# untitled2.net
KiCad netlist of a schematic drawn in EAGLE
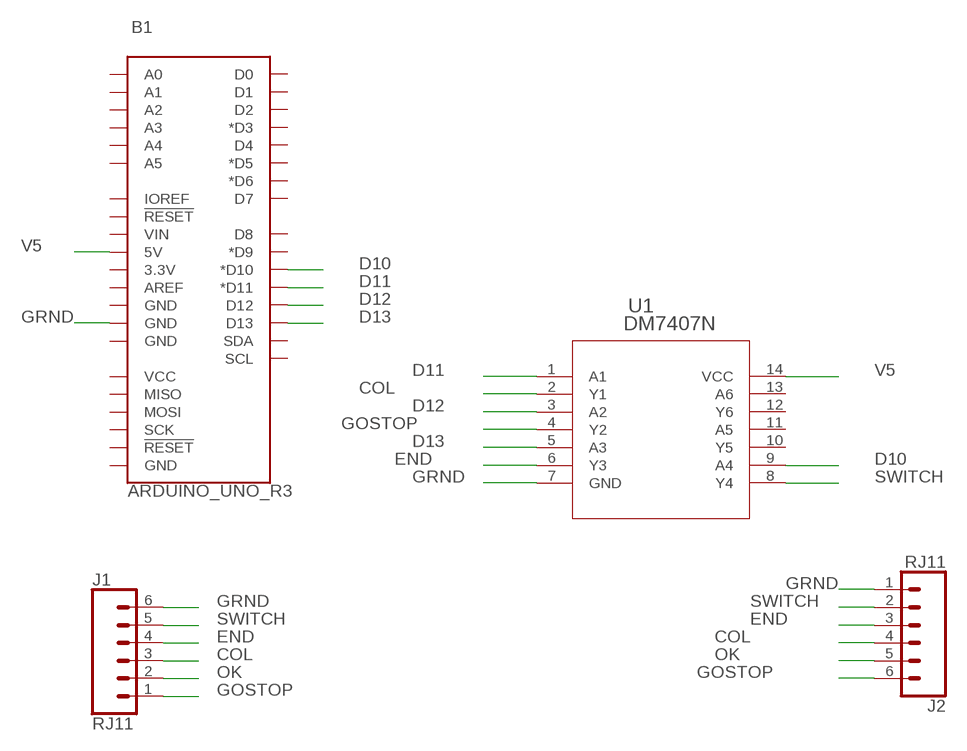
[diagram p0: schematic, sheet 1]

(export (version "E")
  (design (tool "Eeschema 10.0.6"))
  (components
    (comp (ref "B1")
      (value "ARDUINO_UNO_R3")
      (footprint "eagle-import:ARDUINO_R3")
      (libsource (lib "eagle-import") (part "ARDUINO_UNO_R3"))
    )
    (comp (ref "J1")
      (value "RJ11")
      (footprint "eagle-import:RJ11-6")
      (libsource (lib "eagle-import") (part "RJ11-6"))
    )
    (comp (ref "J2")
      (value "RJ11")
      (footprint "eagle-import:RJ11-6")
      (libsource (lib "eagle-import") (part "RJ11-6"))
    )
    (comp (ref "U1")
      (value "DM7407N")
      (footprint "eagle-import:PDIP14_6P35X19P56_ONS")
      (fields (field (name "COPYRIGHT") "Copyright (C) 2024 Ultra Librarian. All rights reserved."))
      (libsource (lib "eagle-import") (part "DM7407N"))
    )
  )
  (nets
    (net (code "1") (name "/COL") (class "Default")
      (node (ref "J1") (pin "3") (pinfunction "3_3") (pintype "passive"))
      (node (ref "J2") (pin "4") (pinfunction "4_4") (pintype "passive"))
      (node (ref "U1") (pin "2") (pinfunction "Y1_2") (pintype "output"))
    )
    (net (code "2") (name "/D10") (class "Default")
      (node (ref "B1") (pin "D10") (pinfunction "*D10_D10") (pintype "bidirectional"))
      (node (ref "U1") (pin "9") (pinfunction "A4_9") (pintype "input"))
    )
    (net (code "3") (name "/D11") (class "Default")
      (node (ref "B1") (pin "D11") (pinfunction "*D11_D11") (pintype "bidirectional"))
      (node (ref "U1") (pin "1") (pinfunction "A1_1") (pintype "input"))
    )
    (net (code "4") (name "/D12") (class "Default")
      (node (ref "B1") (pin "D12") (pinfunction "D12_D12") (pintype "bidirectional"))
      (node (ref "U1") (pin "3") (pinfunction "A2_3") (pintype "input"))
    )
    (net (code "5") (name "/D13") (class "Default")
      (node (ref "B1") (pin "D13") (pinfunction "D13_D13") (pintype "bidirectional"))
      (node (ref "U1") (pin "5") (pinfunction "A3_5") (pintype "input"))
    )
    (net (code "6") (name "/END") (class "Default")
      (node (ref "J1") (pin "4") (pinfunction "4_4") (pintype "passive"))
      (node (ref "J2") (pin "3") (pinfunction "3_3") (pintype "passive"))
      (node (ref "U1") (pin "6") (pinfunction "Y3_6") (pintype "output"))
    )
    (net (code "7") (name "/GOSTOP") (class "Default")
      (node (ref "J1") (pin "1") (pinfunction "1_1") (pintype "passive"))
      (node (ref "J2") (pin "6") (pinfunction "6_6") (pintype "passive"))
      (node (ref "U1") (pin "4") (pinfunction "Y2_4") (pintype "output"))
    )
    (net (code "8") (name "/GRND") (class "Default")
      (node (ref "B1") (pin "GND@3") (pinfunction "GND_GND@3") (pintype "bidirectional"))
      (node (ref "J1") (pin "6") (pinfunction "6_6") (pintype "passive"))
      (node (ref "J2") (pin "1") (pinfunction "1_1") (pintype "passive"))
      (node (ref "U1") (pin "7") (pinfunction "GND_7") (pintype "power_in"))
    )
    (net (code "9") (name "/OK") (class "Default")
      (node (ref "J1") (pin "2") (pinfunction "2_2") (pintype "passive"))
      (node (ref "J2") (pin "5") (pinfunction "5_5") (pintype "passive"))
    )
    (net (code "10") (name "/SWITCH") (class "Default")
      (node (ref "J1") (pin "5") (pinfunction "5_5") (pintype "passive"))
      (node (ref "J2") (pin "2") (pinfunction "2_2") (pintype "passive"))
      (node (ref "U1") (pin "8") (pinfunction "Y4_8") (pintype "output"))
    )
    (net (code "11") (name "/V5") (class "Default")
      (node (ref "B1") (pin "5V") (pinfunction "5V_5V") (pintype "bidirectional"))
      (node (ref "U1") (pin "14") (pinfunction "VCC_14") (pintype "power_in"))
    )
    (net (code "12") (name "unconnected-(B1-*D3-PadD3)") (class "Default")
      (node (ref "B1") (pin "D3") (pinfunction "*D3_D3") (pintype "bidirectional"))
    )
    (net (code "13") (name "unconnected-(B1-*D5-PadD5)") (class "Default")
      (node (ref "B1") (pin "D5") (pinfunction "*D5_D5") (pintype "bidirectional"))
    )
    (net (code "14") (name "unconnected-(B1-*D6-PadD6)") (class "Default")
      (node (ref "B1") (pin "D6") (pinfunction "*D6_D6") (pintype "bidirectional"))
    )
    (net (code "15") (name "unconnected-(B1-*D9-PadD9)") (class "Default")
      (node (ref "B1") (pin "D9") (pinfunction "*D9_D9") (pintype "bidirectional"))
    )
    (net (code "16") (name "unconnected-(B1-GND-PadGND@1)") (class "Default")
      (node (ref "B1") (pin "GND@1") (pinfunction "GND_GND@1") (pintype "bidirectional"))
    )
    (net (code "17") (name "unconnected-(B1-GND-PadGND@2)") (class "Default")
      (node (ref "B1") (pin "GND@2") (pinfunction "GND_GND@2") (pintype "bidirectional"))
    )
    (net (code "18") (name "unconnected-(B1-GND-PadGND@4)") (class "Default")
      (node (ref "B1") (pin "GND@4") (pinfunction "GND_GND@4") (pintype "bidirectional"))
    )
    (net (code "19") (name "unconnected-(B1-Pad3.3V)") (class "Default")
      (node (ref "B1") (pin "3.3V") (pinfunction "3.3V_3.3V") (pintype "bidirectional"))
    )
    (net (code "20") (name "unconnected-(B1-PadA0)") (class "Default")
      (node (ref "B1") (pin "A0") (pinfunction "A0_A0") (pintype "bidirectional"))
    )
    (net (code "21") (name "unconnected-(B1-PadA1)") (class "Default")
      (node (ref "B1") (pin "A1") (pinfunction "A1_A1") (pintype "bidirectional"))
    )
    (net (code "22") (name "unconnected-(B1-PadA2)") (class "Default")
      (node (ref "B1") (pin "A2") (pinfunction "A2_A2") (pintype "bidirectional"))
    )
    (net (code "23") (name "unconnected-(B1-PadA3)") (class "Default")
      (node (ref "B1") (pin "A3") (pinfunction "A3_A3") (pintype "bidirectional"))
    )
    (net (code "24") (name "unconnected-(B1-PadA4)") (class "Default")
      (node (ref "B1") (pin "A4") (pinfunction "A4_A4") (pintype "bidirectional"))
    )
    (net (code "25") (name "unconnected-(B1-PadA5)") (class "Default")
      (node (ref "B1") (pin "A5") (pinfunction "A5_A5") (pintype "bidirectional"))
    )
    (net (code "26") (name "unconnected-(B1-PadAREF)") (class "Default")
      (node (ref "B1") (pin "AREF") (pinfunction "AREF_AREF") (pintype "bidirectional"))
    )
    (net (code "27") (name "unconnected-(B1-PadD0)") (class "Default")
      (node (ref "B1") (pin "D0") (pinfunction "D0_D0") (pintype "bidirectional"))
    )
    (net (code "28") (name "unconnected-(B1-PadD1)") (class "Default")
      (node (ref "B1") (pin "D1") (pinfunction "D1_D1") (pintype "bidirectional"))
    )
    (net (code "29") (name "unconnected-(B1-PadD2)") (class "Default")
      (node (ref "B1") (pin "D2") (pinfunction "D2_D2") (pintype "bidirectional"))
    )
    (net (code "30") (name "unconnected-(B1-PadD4)") (class "Default")
      (node (ref "B1") (pin "D4") (pinfunction "D4_D4") (pintype "bidirectional"))
    )
    (net (code "31") (name "unconnected-(B1-PadD7)") (class "Default")
      (node (ref "B1") (pin "D7") (pinfunction "D7_D7") (pintype "bidirectional"))
    )
    (net (code "32") (name "unconnected-(B1-PadD8)") (class "Default")
      (node (ref "B1") (pin "D8") (pinfunction "D8_D8") (pintype "bidirectional"))
    )
    (net (code "33") (name "unconnected-(B1-PadIOREF)") (class "Default")
      (node (ref "B1") (pin "IOREF") (pinfunction "IOREF_IOREF") (pintype "bidirectional"))
    )
    (net (code "34") (name "unconnected-(B1-PadMISO)") (class "Default")
      (node (ref "B1") (pin "MISO") (pinfunction "MISO_MISO") (pintype "bidirectional"))
    )
    (net (code "35") (name "unconnected-(B1-PadMOSI)") (class "Default")
      (node (ref "B1") (pin "MOSI") (pinfunction "MOSI_MOSI") (pintype "bidirectional"))
    )
    (net (code "36") (name "unconnected-(B1-PadSCK)") (class "Default")
      (node (ref "B1") (pin "SCK") (pinfunction "SCK_SCK") (pintype "bidirectional"))
    )
    (net (code "37") (name "unconnected-(B1-PadSCL)") (class "Default")
      (node (ref "B1") (pin "SCL") (pinfunction "SCL_SCL") (pintype "bidirectional"))
    )
    (net (code "38") (name "unconnected-(B1-PadSDA)") (class "Default")
      (node (ref "B1") (pin "SDA") (pinfunction "SDA_SDA") (pintype "bidirectional"))
    )
    (net (code "39") (name "unconnected-(B1-PadVCC)") (class "Default")
      (node (ref "B1") (pin "VCC") (pinfunction "VCC_VCC") (pintype "bidirectional"))
    )
    (net (code "40") (name "unconnected-(B1-PadVIN)") (class "Default")
      (node (ref "B1") (pin "VIN") (pinfunction "VIN_VIN") (pintype "bidirectional"))
    )
    (net (code "41") (name "unconnected-(B1-~{RESET}-PadRESET@1)") (class "Default")
      (node (ref "B1") (pin "RESET@1") (pinfunction "~{RESET}_RESET@1") (pintype "bidirectional"))
    )
    (net (code "42") (name "unconnected-(B1-~{RESET}-PadRESET@2)") (class "Default")
      (node (ref "B1") (pin "RESET@2") (pinfunction "~{RESET}_RESET@2") (pintype "bidirectional"))
    )
    (net (code "43") (name "unconnected-(U1-A5-Pad11)") (class "Default")
      (node (ref "U1") (pin "11") (pinfunction "A5_11") (pintype "input"))
    )
    (net (code "44") (name "unconnected-(U1-A6-Pad13)") (class "Default")
      (node (ref "U1") (pin "13") (pinfunction "A6_13") (pintype "input"))
    )
    (net (code "45") (name "unconnected-(U1-Y5-Pad10)") (class "Default")
      (node (ref "U1") (pin "10") (pinfunction "Y5_10") (pintype "output"))
    )
    (net (code "46") (name "unconnected-(U1-Y6-Pad12)") (class "Default")
      (node (ref "U1") (pin "12") (pinfunction "Y6_12") (pintype "output"))
    )
  )
)
